# pwr.net
KiCad netlist of a schematic drawn in Altium Designer
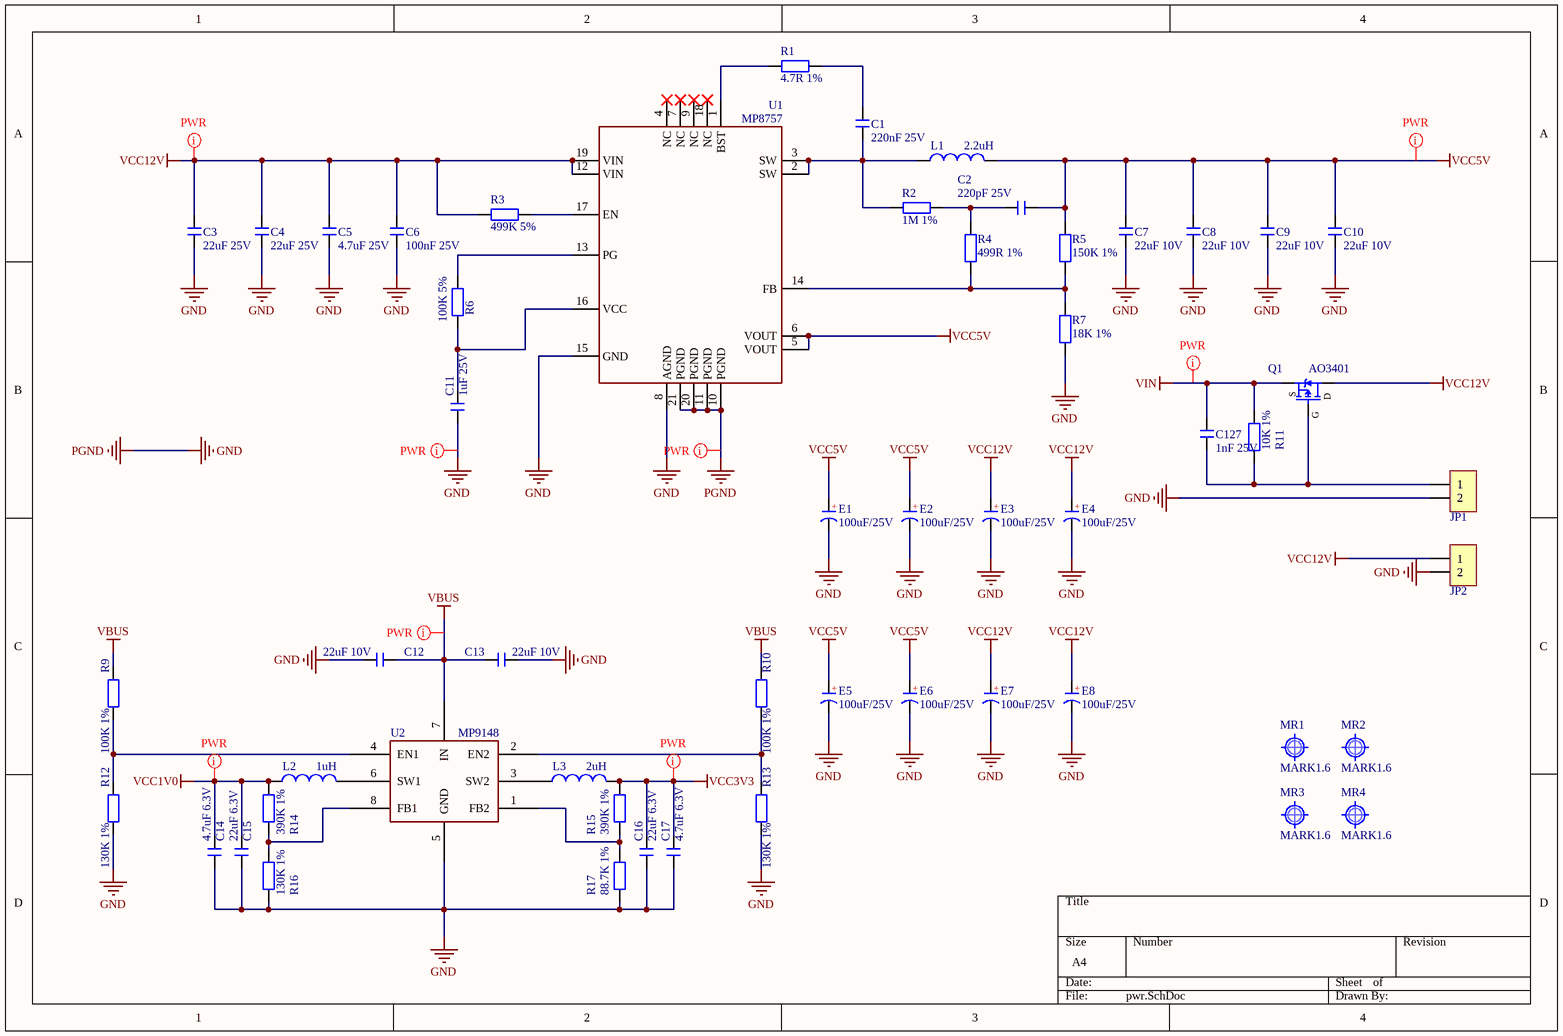
[diagram p0: pwr.SchDoc]

(export (version "E")
  (design (tool "Eeschema 10.0.6"))
  (components
    (comp (ref "C1")
      (value "220nF 25V")
      (footprint "C0402_L")
      (description "无极性贴片电容")
      (fields (field (name "版权归属") "源创客"))
      (libsource (lib "Capacitor") (part "C"))
    )
    (comp (ref "C2")
      (value "220pF 25V")
      (footprint "C0402_L")
      (description "无极性贴片电容")
      (fields (field (name "版权归属") "源创客"))
      (libsource (lib "Capacitor") (part "C"))
    )
    (comp (ref "C3")
      (value "22uF 25V")
      (footprint "C0805_L")
      (description "无极性贴片电容")
      (fields (field (name "版权归属") "源创客"))
      (libsource (lib "Capacitor") (part "C"))
    )
    (comp (ref "C4")
      (value "22uF 25V")
      (footprint "C0805_L")
      (description "无极性贴片电容")
      (fields (field (name "版权归属") "源创客"))
      (libsource (lib "Capacitor") (part "C"))
    )
    (comp (ref "C5")
      (value "4.7uF 25V")
      (footprint "C0805_L")
      (description "无极性贴片电容")
      (fields (field (name "版权归属") "源创客"))
      (libsource (lib "Capacitor") (part "C"))
    )
    (comp (ref "C6")
      (value "100nF 25V")
      (footprint "C0805_L")
      (description "无极性贴片电容")
      (fields (field (name "版权归属") "源创客"))
      (libsource (lib "Capacitor") (part "C"))
    )
    (comp (ref "C7")
      (value "22uF 10V")
      (footprint "C0805_L")
      (description "无极性贴片电容")
      (fields (field (name "版权归属") "源创客"))
      (libsource (lib "Capacitor") (part "C"))
    )
    (comp (ref "C8")
      (value "22uF 10V")
      (footprint "C0805_L")
      (description "无极性贴片电容")
      (fields (field (name "版权归属") "源创客"))
      (libsource (lib "Capacitor") (part "C"))
    )
    (comp (ref "C9")
      (value "22uF 10V")
      (footprint "C0805_L")
      (description "无极性贴片电容")
      (fields (field (name "版权归属") "源创客"))
      (libsource (lib "Capacitor") (part "C"))
    )
    (comp (ref "C10")
      (value "22uF 10V")
      (footprint "C0805_L")
      (description "无极性贴片电容")
      (fields (field (name "版权归属") "源创客"))
      (libsource (lib "Capacitor") (part "C"))
    )
    (comp (ref "C11")
      (value "1uF 25V")
      (footprint "C0402_L")
      (description "无极性贴片电容")
      (fields (field (name "版权归属") "源创客"))
      (libsource (lib "Capacitor") (part "C"))
    )
    (comp (ref "C12")
      (value "22uF 10V")
      (footprint "C0603_L")
      (description "无极性贴片电容")
      (fields (field (name "版权归属") "源创客"))
      (libsource (lib "Capacitor") (part "C"))
    )
    (comp (ref "C13")
      (value "22uF 10V")
      (footprint "C0603_L")
      (description "无极性贴片电容")
      (fields (field (name "版权归属") "源创客"))
      (libsource (lib "Capacitor") (part "C"))
    )
    (comp (ref "C14")
      (value "4.7uF 6.3V")
      (footprint "C0603_L")
      (description "无极性贴片电容")
      (fields (field (name "版权归属") "源创客"))
      (libsource (lib "Capacitor") (part "C"))
    )
    (comp (ref "C15")
      (value "22uF 6.3V")
      (footprint "C0603_L")
      (description "无极性贴片电容")
      (fields (field (name "版权归属") "源创客"))
      (libsource (lib "Capacitor") (part "C"))
    )
    (comp (ref "C16")
      (value "22uF 6.3V")
      (footprint "C0603_L")
      (description "无极性贴片电容")
      (fields (field (name "版权归属") "源创客"))
      (libsource (lib "Capacitor") (part "C"))
    )
    (comp (ref "C17")
      (value "4.7uF 6.3V")
      (footprint "C0603_L")
      (description "无极性贴片电容")
      (fields (field (name "版权归属") "源创客"))
      (libsource (lib "Capacitor") (part "C"))
    )
    (comp (ref "C127")
      (value "1nF 25V")
      (footprint "C0402_L")
      (description "无极性贴片电容")
      (fields (field (name "版权归属") "源创客"))
      (libsource (lib "Capacitor") (part "C"))
    )
    (comp (ref "E1")
      (value "100uF/25V")
      (footprint "CS 6*4 - B")
      (description "贴片钽电容")
      (fields (field (name "版权归属") "源创客"))
      (libsource (lib "Capacitor") (part "C-CD"))
    )
    (comp (ref "E2")
      (value "100uF/25V")
      (footprint "CS 6*4 - B")
      (description "贴片钽电容")
      (fields (field (name "版权归属") "源创客"))
      (libsource (lib "Capacitor") (part "C-CD"))
    )
    (comp (ref "E3")
      (value "100uF/25V")
      (footprint "CS 6*4 - B")
      (description "贴片钽电容")
      (fields (field (name "版权归属") "源创客"))
      (libsource (lib "Capacitor") (part "C-CD"))
    )
    (comp (ref "E4")
      (value "100uF/25V")
      (footprint "CS 6*4 - B")
      (description "贴片钽电容")
      (fields (field (name "版权归属") "源创客"))
      (libsource (lib "Capacitor") (part "C-CD"))
    )
    (comp (ref "E5")
      (value "100uF/25V")
      (footprint "CS 6*4 - B")
      (description "贴片钽电容")
      (fields (field (name "版权归属") "源创客"))
      (libsource (lib "Capacitor") (part "C-CD"))
    )
    (comp (ref "E6")
      (value "100uF/25V")
      (footprint "CS 6*4 - B")
      (description "贴片钽电容")
      (fields (field (name "版权归属") "源创客"))
      (libsource (lib "Capacitor") (part "C-CD"))
    )
    (comp (ref "E7")
      (value "100uF/25V")
      (footprint "CS 6*4 - B")
      (description "贴片钽电容")
      (fields (field (name "版权归属") "源创客"))
      (libsource (lib "Capacitor") (part "C-CD"))
    )
    (comp (ref "E8")
      (value "100uF/25V")
      (footprint "CS 6*4 - B")
      (description "贴片钽电容")
      (fields (field (name "版权归属") "源创客"))
      (libsource (lib "Capacitor") (part "C-CD"))
    )
    (comp (ref "JP1")
      (value "HDR-1X2")
      (footprint "ZH1.5-WS-2P")
      (description "2P接插件")
      (fields (field (name "版权归属") "源创客"))
      (libsource (lib "Connector-PinHeader") (part "Header 2"))
    )
    (comp (ref "JP2")
      (value "HDR-1X2")
      (footprint "XH2.54-WS-2P")
      (description "2P接插件")
      (fields (field (name "版权归属") "源创客"))
      (libsource (lib "Connector-PinHeader") (part "Header 2"))
    )
    (comp (ref "L1")
      (value "2.2uH")
      (footprint "NR8040")
      (description "小功率贴片电感")
      (fields (field (name "版权归属") "源创客"))
      (libsource (lib "") (part "L_1"))
    )
    (comp (ref "L2")
      (value "1uH")
      (footprint "NR4020")
      (description "小功率贴片电感")
      (fields (field (name "版权归属") "源创客"))
      (libsource (lib "Inductor") (part "L"))
    )
    (comp (ref "L3")
      (value "2uH")
      (footprint "NR4020")
      (description "小功率贴片电感")
      (fields (field (name "版权归属") "源创客"))
      (libsource (lib "") (part "L_1"))
    )
    (comp (ref "MR1")
      (value "MARK1.6")
      (footprint "Mark 1")
      (description "光学定位点")
      (fields (field (name "版权归属") "源创客"))
      (libsource (lib "Hole") (part "MARK"))
    )
    (comp (ref "MR2")
      (value "MARK1.6")
      (footprint "Mark 1")
      (description "光学定位点")
      (fields (field (name "版权归属") "源创客"))
      (libsource (lib "Hole") (part "MARK"))
    )
    (comp (ref "MR3")
      (value "MARK1.6")
      (footprint "Mark 1")
      (description "光学定位点")
      (fields (field (name "版权归属") "源创客"))
      (libsource (lib "Hole") (part "MARK"))
    )
    (comp (ref "MR4")
      (value "MARK1.6")
      (footprint "Mark 1")
      (description "光学定位点")
      (fields (field (name "版权归属") "源创客"))
      (libsource (lib "Hole") (part "MARK"))
    )
    (comp (ref "Q1")
      (value "AO3401")
      (footprint "DFN8-L3.0-W3.0-P0.65_EP")
      (description "P沟道 30V/4.2A")
      (fields (field (name "版权归属") "源创客"))
      (libsource (lib "MOSFET BJT IGBT") (part "AO3401"))
    )
    (comp (ref "R1")
      (value "4.7R 1%")
      (footprint "R0402_L")
      (description "贴片电阻")
      (fields (field (name "版权归属") "源创客"))
      (libsource (lib "Resistor") (part "R"))
    )
    (comp (ref "R2")
      (value "1M 1%")
      (footprint "R0402_L")
      (description "贴片电阻")
      (fields (field (name "版权归属") "源创客"))
      (libsource (lib "Resistor") (part "R"))
    )
    (comp (ref "R3")
      (value "499K 5%")
      (footprint "R0402_L")
      (description "贴片电阻")
      (fields (field (name "版权归属") "源创客"))
      (libsource (lib "Resistor") (part "R"))
    )
    (comp (ref "R4")
      (value "499R 1%")
      (footprint "R0402_L")
      (description "贴片电阻")
      (fields (field (name "版权归属") "源创客"))
      (libsource (lib "Resistor") (part "R"))
    )
    (comp (ref "R5")
      (value "150K 1%")
      (footprint "R0402_L")
      (description "贴片电阻")
      (fields (field (name "版权归属") "源创客"))
      (libsource (lib "Resistor") (part "R"))
    )
    (comp (ref "R6")
      (value "100K 5%")
      (footprint "R0402_L")
      (description "贴片电阻")
      (fields (field (name "版权归属") "源创客"))
      (libsource (lib "Resistor") (part "R"))
    )
    (comp (ref "R7")
      (value "18K 1%")
      (footprint "R0402_L")
      (description "贴片电阻")
      (fields (field (name "版权归属") "源创客"))
      (libsource (lib "Resistor") (part "R"))
    )
    (comp (ref "R9")
      (value "100K 1%")
      (footprint "R0402_L")
      (description "贴片电阻")
      (fields (field (name "版权归属") "源创客"))
      (libsource (lib "Resistor") (part "R"))
    )
    (comp (ref "R10")
      (value "100K 1%")
      (footprint "R0402_L")
      (description "贴片电阻")
      (fields (field (name "版权归属") "源创客"))
      (libsource (lib "Resistor") (part "R"))
    )
    (comp (ref "R11")
      (value "10K 1%")
      (footprint "R0402_L")
      (description "贴片电阻")
      (fields (field (name "版权归属") "源创客"))
      (libsource (lib "Resistor") (part "R"))
    )
    (comp (ref "R12")
      (value "130K 1%")
      (footprint "R0402_L")
      (description "贴片电阻")
      (fields (field (name "版权归属") "源创客"))
      (libsource (lib "Resistor") (part "R"))
    )
    (comp (ref "R13")
      (value "130K 1%")
      (footprint "R0402_L")
      (description "贴片电阻")
      (fields (field (name "版权归属") "源创客"))
      (libsource (lib "Resistor") (part "R"))
    )
    (comp (ref "R14")
      (value "390K 1%")
      (footprint "R0402_L")
      (description "贴片电阻")
      (fields (field (name "版权归属") "源创客"))
      (libsource (lib "Resistor") (part "R"))
    )
    (comp (ref "R15")
      (value "390K 1%")
      (footprint "R0402_L")
      (description "贴片电阻")
      (fields (field (name "版权归属") "源创客"))
      (libsource (lib "Resistor") (part "R"))
    )
    (comp (ref "R16")
      (value "130K 1%")
      (footprint "R0402_L")
      (description "贴片电阻")
      (fields (field (name "版权归属") "源创客"))
      (libsource (lib "Resistor") (part "R"))
    )
    (comp (ref "R17")
      (value "88.7K 1%")
      (footprint "R0402_L")
      (description "贴片电阻")
      (fields (field (name "版权归属") "源创客"))
      (libsource (lib "Resistor") (part "R"))
    )
    (comp (ref "U1")
      (value "MP8757")
      (footprint "MP8757")
      (description "DCDC控制器")
      (libsource (lib "DCDC Convert") (part "MP8757"))
    )
    (comp (ref "U2")
      (value "MP9148")
      (footprint "SOT23-8")
      (description "BUCK")
      (libsource (lib "DCDC Convert") (part "MP9148"))
    )
  )
  (nets
    (net (code "1") (name "GND") (class "Default")
      (node (ref "C10") (pin "1") (pinfunction "1_1") (pintype "passive"))
      (node (ref "C11") (pin "1") (pinfunction "1_1") (pintype "passive"))
      (node (ref "C12") (pin "1") (pinfunction "1_1") (pintype "passive"))
      (node (ref "C13") (pin "1") (pinfunction "1_1") (pintype "passive"))
      (node (ref "C14") (pin "1") (pinfunction "1_1") (pintype "passive"))
      (node (ref "C15") (pin "1") (pinfunction "1_1") (pintype "passive"))
      (node (ref "C16") (pin "1") (pinfunction "1_1") (pintype "passive"))
      (node (ref "C17") (pin "1") (pinfunction "1_1") (pintype "passive"))
      (node (ref "C3") (pin "1") (pinfunction "1_1") (pintype "passive"))
      (node (ref "C4") (pin "1") (pinfunction "1_1") (pintype "passive"))
      (node (ref "C5") (pin "1") (pinfunction "1_1") (pintype "passive"))
      (node (ref "C6") (pin "1") (pinfunction "1_1") (pintype "passive"))
      (node (ref "C7") (pin "1") (pinfunction "1_1") (pintype "passive"))
      (node (ref "C8") (pin "1") (pinfunction "1_1") (pintype "passive"))
      (node (ref "C9") (pin "1") (pinfunction "1_1") (pintype "passive"))
      (node (ref "E1") (pin "2") (pinfunction "K_2") (pintype "passive"))
      (node (ref "E2") (pin "2") (pinfunction "K_2") (pintype "passive"))
      (node (ref "E3") (pin "2") (pinfunction "K_2") (pintype "passive"))
      (node (ref "E4") (pin "2") (pinfunction "K_2") (pintype "passive"))
      (node (ref "E5") (pin "2") (pinfunction "K_2") (pintype "passive"))
      (node (ref "E6") (pin "2") (pinfunction "K_2") (pintype "passive"))
      (node (ref "E7") (pin "2") (pinfunction "K_2") (pintype "passive"))
      (node (ref "E8") (pin "2") (pinfunction "K_2") (pintype "passive"))
      (node (ref "JP1") (pin "2") (pinfunction "2_2") (pintype "passive"))
      (node (ref "JP2") (pin "2") (pinfunction "2_2") (pintype "passive"))
      (node (ref "R12") (pin "2") (pinfunction "2_2") (pintype "passive"))
      (node (ref "R13") (pin "2") (pinfunction "2_2") (pintype "passive"))
      (node (ref "R16") (pin "2") (pinfunction "2_2") (pintype "passive"))
      (node (ref "R17") (pin "2") (pinfunction "2_2") (pintype "passive"))
      (node (ref "R7") (pin "1") (pinfunction "1_1") (pintype "passive"))
      (node (ref "U1") (pin "10") (pinfunction "PGND_10") (pintype "passive"))
      (node (ref "U1") (pin "11") (pinfunction "PGND_11") (pintype "passive"))
      (node (ref "U1") (pin "15") (pinfunction "GND_15") (pintype "passive"))
      (node (ref "U1") (pin "20") (pinfunction "PGND_20") (pintype "passive"))
      (node (ref "U1") (pin "21") (pinfunction "PGND_21") (pintype "passive"))
      (node (ref "U1") (pin "8") (pinfunction "AGND_8") (pintype "passive"))
      (node (ref "U2") (pin "5") (pinfunction "GND_5") (pintype "passive"))
    )
    (net (code "2") (name "Net-(C1-Pad1)") (class "Default")
      (node (ref "C1") (pin "1") (pinfunction "1_1") (pintype "passive"))
      (node (ref "R1") (pin "2") (pinfunction "2_2") (pintype "passive"))
    )
    (net (code "3") (name "Net-(C1-Pad2)") (class "Default")
      (node (ref "C1") (pin "2") (pinfunction "2_2") (pintype "passive"))
      (node (ref "L1") (pin "2") (pinfunction "2_2") (pintype "passive"))
      (node (ref "R2") (pin "1") (pinfunction "1_1") (pintype "passive"))
      (node (ref "U1") (pin "2") (pinfunction "SW_2") (pintype "passive"))
      (node (ref "U1") (pin "3") (pinfunction "SW_3") (pintype "passive"))
    )
    (net (code "4") (name "Net-(C2-Pad2)") (class "Default")
      (node (ref "C2") (pin "2") (pinfunction "2_2") (pintype "passive"))
      (node (ref "R2") (pin "2") (pinfunction "2_2") (pintype "passive"))
      (node (ref "R4") (pin "1") (pinfunction "1_1") (pintype "passive"))
    )
    (net (code "5") (name "Net-(Q1-G)") (class "Default")
      (node (ref "C127") (pin "2") (pinfunction "2_2") (pintype "passive"))
      (node (ref "JP1") (pin "1") (pinfunction "1_1") (pintype "passive"))
      (node (ref "Q1") (pin "1") (pinfunction "G_1") (pintype "passive"))
      (node (ref "R11") (pin "2") (pinfunction "2_2") (pintype "passive"))
    )
    (net (code "6") (name "Net-(U1-BST)") (class "Default")
      (node (ref "R1") (pin "1") (pinfunction "1_1") (pintype "passive"))
      (node (ref "U1") (pin "1") (pinfunction "BST_1") (pintype "passive"))
    )
    (net (code "7") (name "Net-(U1-EN)") (class "Default")
      (node (ref "R3") (pin "2") (pinfunction "2_2") (pintype "passive"))
      (node (ref "U1") (pin "17") (pinfunction "EN_17") (pintype "passive"))
    )
    (net (code "8") (name "Net-(U1-FB)") (class "Default")
      (node (ref "R4") (pin "2") (pinfunction "2_2") (pintype "passive"))
      (node (ref "R5") (pin "1") (pinfunction "1_1") (pintype "passive"))
      (node (ref "R7") (pin "2") (pinfunction "2_2") (pintype "passive"))
      (node (ref "U1") (pin "14") (pinfunction "FB_14") (pintype "passive"))
    )
    (net (code "9") (name "Net-(U1-PG)") (class "Default")
      (node (ref "R6") (pin "2") (pinfunction "2_2") (pintype "passive"))
      (node (ref "U1") (pin "13") (pinfunction "PG_13") (pintype "passive"))
    )
    (net (code "10") (name "Net-(U1-VCC)") (class "Default")
      (node (ref "C11") (pin "2") (pinfunction "2_2") (pintype "passive"))
      (node (ref "R6") (pin "1") (pinfunction "1_1") (pintype "passive"))
      (node (ref "U1") (pin "16") (pinfunction "VCC_16") (pintype "passive"))
    )
    (net (code "11") (name "Net-(U2-EN1)") (class "Default")
      (node (ref "R12") (pin "1") (pinfunction "1_1") (pintype "passive"))
      (node (ref "R9") (pin "2") (pinfunction "2_2") (pintype "passive"))
      (node (ref "U2") (pin "4") (pinfunction "EN1_4") (pintype "passive"))
    )
    (net (code "12") (name "Net-(U2-EN2)") (class "Default")
      (node (ref "R10") (pin "2") (pinfunction "2_2") (pintype "passive"))
      (node (ref "R13") (pin "1") (pinfunction "1_1") (pintype "passive"))
      (node (ref "U2") (pin "2") (pinfunction "EN2_2") (pintype "passive"))
    )
    (net (code "13") (name "Net-(U2-FB1)") (class "Default")
      (node (ref "R14") (pin "2") (pinfunction "2_2") (pintype "passive"))
      (node (ref "R16") (pin "1") (pinfunction "1_1") (pintype "passive"))
      (node (ref "U2") (pin "8") (pinfunction "FB1_8") (pintype "passive"))
    )
    (net (code "14") (name "Net-(U2-FB2)") (class "Default")
      (node (ref "R15") (pin "2") (pinfunction "2_2") (pintype "passive"))
      (node (ref "R17") (pin "1") (pinfunction "1_1") (pintype "passive"))
      (node (ref "U2") (pin "1") (pinfunction "FB2_1") (pintype "passive"))
    )
    (net (code "15") (name "Net-(U2-SW1)") (class "Default")
      (node (ref "L2") (pin "2") (pinfunction "2_2") (pintype "passive"))
      (node (ref "U2") (pin "6") (pinfunction "SW1_6") (pintype "passive"))
    )
    (net (code "16") (name "Net-(U2-SW2)") (class "Default")
      (node (ref "L3") (pin "2") (pinfunction "2_2") (pintype "passive"))
      (node (ref "U2") (pin "3") (pinfunction "SW2_3") (pintype "passive"))
    )
    (net (code "17") (name "VBUS") (class "Default")
      (node (ref "C12") (pin "2") (pinfunction "2_2") (pintype "passive"))
      (node (ref "C13") (pin "2") (pinfunction "2_2") (pintype "passive"))
      (node (ref "R10") (pin "1") (pinfunction "1_1") (pintype "passive"))
      (node (ref "R9") (pin "1") (pinfunction "1_1") (pintype "passive"))
      (node (ref "U2") (pin "7") (pinfunction "IN_7") (pintype "passive"))
    )
    (net (code "18") (name "VCC1V0") (class "Default")
      (node (ref "C14") (pin "2") (pinfunction "2_2") (pintype "passive"))
      (node (ref "C15") (pin "2") (pinfunction "2_2") (pintype "passive"))
      (node (ref "L2") (pin "1") (pinfunction "1_1") (pintype "passive"))
      (node (ref "R14") (pin "1") (pinfunction "1_1") (pintype "passive"))
    )
    (net (code "19") (name "VCC3V3") (class "Default")
      (node (ref "C16") (pin "2") (pinfunction "2_2") (pintype "passive"))
      (node (ref "C17") (pin "2") (pinfunction "2_2") (pintype "passive"))
      (node (ref "L3") (pin "1") (pinfunction "1_1") (pintype "passive"))
      (node (ref "R15") (pin "1") (pinfunction "1_1") (pintype "passive"))
    )
    (net (code "20") (name "VCC5V") (class "Default")
      (node (ref "C10") (pin "2") (pinfunction "2_2") (pintype "passive"))
      (node (ref "C2") (pin "1") (pinfunction "1_1") (pintype "passive"))
      (node (ref "C7") (pin "2") (pinfunction "2_2") (pintype "passive"))
      (node (ref "C8") (pin "2") (pinfunction "2_2") (pintype "passive"))
      (node (ref "C9") (pin "2") (pinfunction "2_2") (pintype "passive"))
      (node (ref "E1") (pin "1") (pinfunction "A_1") (pintype "passive"))
      (node (ref "E2") (pin "1") (pinfunction "A_1") (pintype "passive"))
      (node (ref "E5") (pin "1") (pinfunction "A_1") (pintype "passive"))
      (node (ref "E6") (pin "1") (pinfunction "A_1") (pintype "passive"))
      (node (ref "L1") (pin "1") (pinfunction "1_1") (pintype "passive"))
      (node (ref "R5") (pin "2") (pinfunction "2_2") (pintype "passive"))
      (node (ref "U1") (pin "5") (pinfunction "VOUT_5") (pintype "passive"))
      (node (ref "U1") (pin "6") (pinfunction "VOUT_6") (pintype "passive"))
    )
    (net (code "21") (name "VCC12V") (class "Default")
      (node (ref "C3") (pin "2") (pinfunction "2_2") (pintype "passive"))
      (node (ref "C4") (pin "2") (pinfunction "2_2") (pintype "passive"))
      (node (ref "C5") (pin "2") (pinfunction "2_2") (pintype "passive"))
      (node (ref "C6") (pin "2") (pinfunction "2_2") (pintype "passive"))
      (node (ref "E3") (pin "1") (pinfunction "A_1") (pintype "passive"))
      (node (ref "E4") (pin "1") (pinfunction "A_1") (pintype "passive"))
      (node (ref "E7") (pin "1") (pinfunction "A_1") (pintype "passive"))
      (node (ref "E8") (pin "1") (pinfunction "A_1") (pintype "passive"))
      (node (ref "JP2") (pin "1") (pinfunction "1_1") (pintype "passive"))
      (node (ref "Q1") (pin "3") (pinfunction "D_3") (pintype "passive"))
      (node (ref "R3") (pin "1") (pinfunction "1_1") (pintype "passive"))
      (node (ref "U1") (pin "12") (pinfunction "VIN_12") (pintype "passive"))
      (node (ref "U1") (pin "19") (pinfunction "VIN_19") (pintype "passive"))
    )
    (net (code "22") (name "VIN") (class "Default")
      (node (ref "C127") (pin "1") (pinfunction "1_1") (pintype "passive"))
      (node (ref "Q1") (pin "2") (pinfunction "S_2") (pintype "passive"))
      (node (ref "R11") (pin "1") (pinfunction "1_1") (pintype "passive"))
    )
    (net (code "23") (name "unconnected-(U1-NC-Pad4)") (class "Default")
      (node (ref "U1") (pin "4") (pinfunction "NC_4") (pintype "passive+no_connect"))
    )
    (net (code "24") (name "unconnected-(U1-NC-Pad7)") (class "Default")
      (node (ref "U1") (pin "7") (pinfunction "NC_7") (pintype "passive+no_connect"))
    )
    (net (code "25") (name "unconnected-(U1-NC-Pad9)") (class "Default")
      (node (ref "U1") (pin "9") (pinfunction "NC_9") (pintype "passive+no_connect"))
    )
    (net (code "26") (name "unconnected-(U1-NC-Pad18)") (class "Default")
      (node (ref "U1") (pin "18") (pinfunction "NC_18") (pintype "passive+no_connect"))
    )
  )
)
